# LineMixer_v1_1.net
KiCad netlist of a schematic drawn in EAGLE
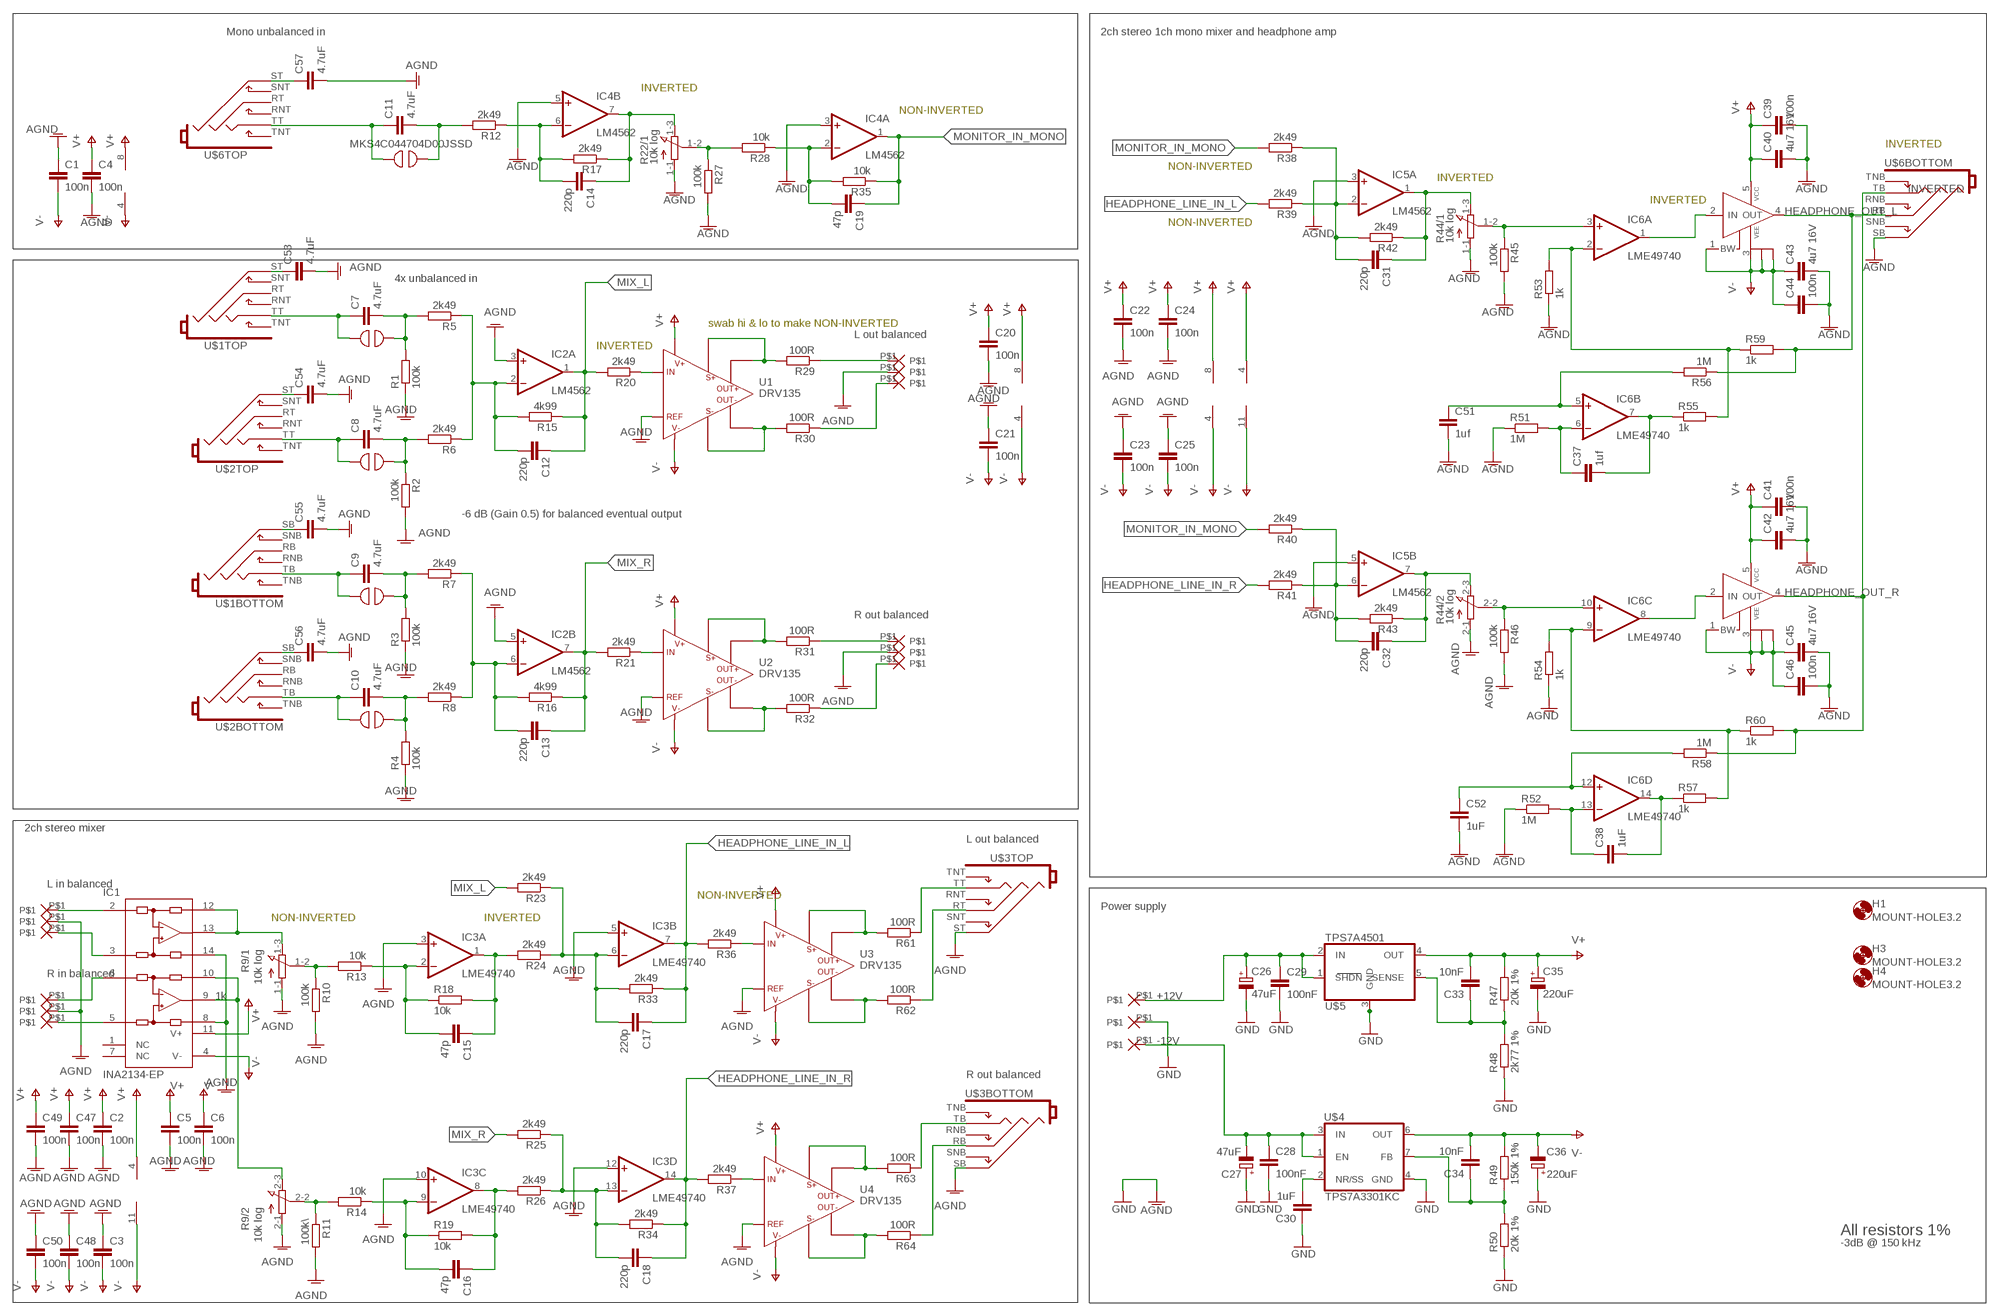
[diagram p0: schematic, sheet 1]

(export (version "E")
  (design (tool "Eeschema 10.0.6"))
  (components
    (comp (ref "C1")
      (value "100n")
      (footprint "eagle-import:C0603")
      (libsource (lib "eagle-import") (part "C-EUC0603"))
    )
    (comp (ref "C2")
      (value "100n")
      (footprint "eagle-import:C0603")
      (libsource (lib "eagle-import") (part "C-EUC0603"))
    )
    (comp (ref "C3")
      (value "100n")
      (footprint "eagle-import:C0603")
      (libsource (lib "eagle-import") (part "C-EUC0603"))
    )
    (comp (ref "C4")
      (value "100n")
      (footprint "eagle-import:C0603")
      (libsource (lib "eagle-import") (part "C-EUC0603"))
    )
    (comp (ref "C5")
      (value "100n")
      (footprint "eagle-import:C0603")
      (libsource (lib "eagle-import") (part "C-EUC0603"))
    )
    (comp (ref "C6")
      (value "100n")
      (footprint "eagle-import:C0603")
      (libsource (lib "eagle-import") (part "C-EUC0603"))
    )
    (comp (ref "C7")
      (value "4.7uF")
      (footprint "eagle-import:C15B7")
      (libsource (lib "eagle-import") (part "C15/7"))
    )
    (comp (ref "C8")
      (value "4.7uF")
      (footprint "eagle-import:C15B7")
      (libsource (lib "eagle-import") (part "C15/7"))
    )
    (comp (ref "C9")
      (value "4.7uF")
      (footprint "eagle-import:C15B7")
      (libsource (lib "eagle-import") (part "C15/7"))
    )
    (comp (ref "C10")
      (value "4.7uF")
      (footprint "eagle-import:C15B7")
      (libsource (lib "eagle-import") (part "C15/7"))
    )
    (comp (ref "C11")
      (value "4.7uF")
      (footprint "eagle-import:C15B7")
      (libsource (lib "eagle-import") (part "C15/7"))
    )
    (comp (ref "C12")
      (value "220p")
      (footprint "eagle-import:C0603K")
      (libsource (lib "eagle-import") (part "C-EUC0603K"))
    )
    (comp (ref "C13")
      (value "220p")
      (footprint "eagle-import:C0603K")
      (libsource (lib "eagle-import") (part "C-EUC0603K"))
    )
    (comp (ref "C14")
      (value "220p")
      (footprint "eagle-import:C0603K")
      (libsource (lib "eagle-import") (part "C-EUC0603K"))
    )
    (comp (ref "C15")
      (value "47p")
      (footprint "eagle-import:C0603K")
      (libsource (lib "eagle-import") (part "C-EUC0603K"))
    )
    (comp (ref "C16")
      (value "47p")
      (footprint "eagle-import:C0603K")
      (libsource (lib "eagle-import") (part "C-EUC0603K"))
    )
    (comp (ref "C17")
      (value "220p")
      (footprint "eagle-import:C0603K")
      (libsource (lib "eagle-import") (part "C-EUC0603K"))
    )
    (comp (ref "C18")
      (value "220p")
      (footprint "eagle-import:C0603K")
      (libsource (lib "eagle-import") (part "C-EUC0603K"))
    )
    (comp (ref "C19")
      (value "47p")
      (footprint "eagle-import:C0603K")
      (libsource (lib "eagle-import") (part "C-EUC0603K"))
    )
    (comp (ref "C20")
      (value "100n")
      (footprint "eagle-import:C0603")
      (libsource (lib "eagle-import") (part "C-EUC0603"))
    )
    (comp (ref "C21")
      (value "100n")
      (footprint "eagle-import:C0603")
      (libsource (lib "eagle-import") (part "C-EUC0603"))
    )
    (comp (ref "C22")
      (value "100n")
      (footprint "eagle-import:C0603")
      (libsource (lib "eagle-import") (part "C-EUC0603"))
    )
    (comp (ref "C23")
      (value "100n")
      (footprint "eagle-import:C0603")
      (libsource (lib "eagle-import") (part "C-EUC0603"))
    )
    (comp (ref "C24")
      (value "100n")
      (footprint "eagle-import:C0603")
      (libsource (lib "eagle-import") (part "C-EUC0603"))
    )
    (comp (ref "C25")
      (value "100n")
      (footprint "eagle-import:C0603")
      (libsource (lib "eagle-import") (part "C-EUC0603"))
    )
    (comp (ref "C26")
      (value "47uF")
      (footprint "eagle-import:D_7343-31R")
      (libsource (lib "eagle-import") (part "CPOL-EUD/7343-31R"))
    )
    (comp (ref "C27")
      (value "47uF")
      (footprint "eagle-import:D_7343-31R")
      (libsource (lib "eagle-import") (part "CPOL-EUD/7343-31R"))
    )
    (comp (ref "C28")
      (value "100nF")
      (footprint "eagle-import:C0603")
      (libsource (lib "eagle-import") (part "C-EUC0603"))
    )
    (comp (ref "C29")
      (value "100nF")
      (footprint "eagle-import:C0603")
      (libsource (lib "eagle-import") (part "C-EUC0603"))
    )
    (comp (ref "C30")
      (value "1uF")
      (footprint "eagle-import:C0603")
      (libsource (lib "eagle-import") (part "C-EUC0603"))
    )
    (comp (ref "C31")
      (value "220p")
      (footprint "eagle-import:C0603K")
      (libsource (lib "eagle-import") (part "C-EUC0603K"))
    )
    (comp (ref "C32")
      (value "220p")
      (footprint "eagle-import:C0603K")
      (libsource (lib "eagle-import") (part "C-EUC0603K"))
    )
    (comp (ref "C33")
      (value "10nF")
      (footprint "eagle-import:C0603")
      (libsource (lib "eagle-import") (part "C-EUC0603"))
    )
    (comp (ref "C34")
      (value "10nF")
      (footprint "eagle-import:C0603")
      (libsource (lib "eagle-import") (part "C-EUC0603"))
    )
    (comp (ref "C35")
      (value "220uF")
      (footprint "eagle-import:D_7343-31R")
      (libsource (lib "eagle-import") (part "CPOL-EUD/7343-31R"))
    )
    (comp (ref "C36")
      (value "220uF")
      (footprint "eagle-import:D_7343-31R")
      (libsource (lib "eagle-import") (part "CPOL-EUD/7343-31R"))
    )
    (comp (ref "C37")
      (value "1uf")
      (footprint "eagle-import:C0603")
      (libsource (lib "eagle-import") (part "C-EUC0603"))
    )
    (comp (ref "C38")
      (value "1uF")
      (footprint "eagle-import:C0603")
      (libsource (lib "eagle-import") (part "C-EUC0603"))
    )
    (comp (ref "C39")
      (value "100n")
      (footprint "eagle-import:C0603")
      (libsource (lib "eagle-import") (part "C-EUC0603"))
    )
    (comp (ref "C40")
      (value "4u7 16V")
      (footprint "eagle-import:C1206")
      (libsource (lib "eagle-import") (part "C-EUC1206"))
    )
    (comp (ref "C41")
      (value "100n")
      (footprint "eagle-import:C0603")
      (libsource (lib "eagle-import") (part "C-EUC0603"))
    )
    (comp (ref "C42")
      (value "4u7 16V")
      (footprint "eagle-import:C1206")
      (libsource (lib "eagle-import") (part "C-EUC1206"))
    )
    (comp (ref "C43")
      (value "4u7 16V")
      (footprint "eagle-import:C1206")
      (libsource (lib "eagle-import") (part "C-EUC1206"))
    )
    (comp (ref "C44")
      (value "100n")
      (footprint "eagle-import:C0603")
      (libsource (lib "eagle-import") (part "C-EUC0603"))
    )
    (comp (ref "C45")
      (value "4u7 16V")
      (footprint "eagle-import:C1206")
      (libsource (lib "eagle-import") (part "C-EUC1206"))
    )
    (comp (ref "C46")
      (value "100n")
      (footprint "eagle-import:C0603")
      (libsource (lib "eagle-import") (part "C-EUC0603"))
    )
    (comp (ref "C47")
      (value "100n")
      (footprint "eagle-import:C0603")
      (libsource (lib "eagle-import") (part "C-EUC0603"))
    )
    (comp (ref "C48")
      (value "100n")
      (footprint "eagle-import:C0603")
      (libsource (lib "eagle-import") (part "C-EUC0603"))
    )
    (comp (ref "C49")
      (value "100n")
      (footprint "eagle-import:C0603")
      (libsource (lib "eagle-import") (part "C-EUC0603"))
    )
    (comp (ref "C50")
      (value "100n")
      (footprint "eagle-import:C0603")
      (libsource (lib "eagle-import") (part "C-EUC0603"))
    )
    (comp (ref "C51")
      (value "1uf")
      (footprint "eagle-import:C0603")
      (libsource (lib "eagle-import") (part "C-EUC0603"))
    )
    (comp (ref "C52")
      (value "1uF")
      (footprint "eagle-import:C0603")
      (libsource (lib "eagle-import") (part "C-EUC0603"))
    )
    (comp (ref "C53")
      (value "4.7uF")
      (footprint "eagle-import:C15B7")
      (libsource (lib "eagle-import") (part "C15/7"))
    )
    (comp (ref "C54")
      (value "4.7uF")
      (footprint "eagle-import:C15B7")
      (libsource (lib "eagle-import") (part "C15/7"))
    )
    (comp (ref "C55")
      (value "4.7uF")
      (footprint "eagle-import:C15B7")
      (libsource (lib "eagle-import") (part "C15/7"))
    )
    (comp (ref "C56")
      (value "4.7uF")
      (footprint "eagle-import:C15B7")
      (libsource (lib "eagle-import") (part "C15/7"))
    )
    (comp (ref "C57")
      (value "4.7uF")
      (footprint "eagle-import:C15B7")
      (libsource (lib "eagle-import") (part "C15/7"))
    )
    (comp (ref "H1")
      (value "MOUNT-HOLE3.2")
      (footprint "eagle-import:3,2")
      (libsource (lib "eagle-import") (part "MOUNT-HOLE3.2"))
    )
    (comp (ref "H3")
      (value "MOUNT-HOLE3.2")
      (footprint "eagle-import:3,2")
      (libsource (lib "eagle-import") (part "MOUNT-HOLE3.2"))
    )
    (comp (ref "H4")
      (value "MOUNT-HOLE3.2")
      (footprint "eagle-import:3,2")
      (libsource (lib "eagle-import") (part "MOUNT-HOLE3.2"))
    )
    (comp (ref "IC1")
      (value "INA2134-EP")
      (footprint "eagle-import:SO14")
      (fields (field (name "MF") "TEXAS INSTRUMENTS") (field (name "MPN") "INA2134UA"))
      (libsource (lib "eagle-import") (part "INA2134U"))
    )
    (comp (ref "IC2")
      (value "LM4562")
      (footprint "eagle-import:SO08")
      (libsource (lib "eagle-import") (part "4558DLM"))
    )
    (comp (ref "IC3")
      (value "LME49740")
      (footprint "eagle-import:SO14")
      (libsource (lib "eagle-import") (part "TL074D"))
    )
    (comp (ref "IC4")
      (value "LM4562")
      (footprint "eagle-import:SO08")
      (libsource (lib "eagle-import") (part "4558DLM"))
    )
    (comp (ref "IC5")
      (value "LM4562")
      (footprint "eagle-import:SO08")
      (libsource (lib "eagle-import") (part "4558DLM"))
    )
    (comp (ref "IC6")
      (value "LME49740")
      (footprint "eagle-import:SO14")
      (libsource (lib "eagle-import") (part "TL074D"))
    )
    (comp (ref "IC7")
      (value "LME49600")
      (footprint "eagle-import:TS5B")
      (libsource (lib "eagle-import") (part "LME49600"))
    )
    (comp (ref "IC8")
      (value "LME49600")
      (footprint "eagle-import:TS5B")
      (libsource (lib "eagle-import") (part "LME49600"))
    )
    (comp (ref "R1")
      (value "100k")
      (footprint "eagle-import:0207_7")
      (libsource (lib "eagle-import") (part "R-EU_0207/7"))
    )
    (comp (ref "R2")
      (value "100k")
      (footprint "eagle-import:0207_7")
      (libsource (lib "eagle-import") (part "R-EU_0207/7"))
    )
    (comp (ref "R3")
      (value "100k")
      (footprint "eagle-import:0207_7")
      (libsource (lib "eagle-import") (part "R-EU_0207/7"))
    )
    (comp (ref "R4")
      (value "100k")
      (footprint "eagle-import:0207_7")
      (libsource (lib "eagle-import") (part "R-EU_0207/7"))
    )
    (comp (ref "R5")
      (value "2k49")
      (footprint "eagle-import:0207_7")
      (libsource (lib "eagle-import") (part "R-EU_0207/7"))
    )
    (comp (ref "R6")
      (value "2k49")
      (footprint "eagle-import:0207_7")
      (libsource (lib "eagle-import") (part "R-EU_0207/7"))
    )
    (comp (ref "R7")
      (value "2k49")
      (footprint "eagle-import:0207_7")
      (libsource (lib "eagle-import") (part "R-EU_0207/7"))
    )
    (comp (ref "R8")
      (value "2k49")
      (footprint "eagle-import:0207_7")
      (libsource (lib "eagle-import") (part "R-EU_0207/7"))
    )
    (comp (ref "R9")
      (value "10k log")
      (footprint "eagle-import:3RP_1610G")
      (libsource (lib "eagle-import") (part "3RP/1610G"))
    )
    (comp (ref "R10")
      (value "100k")
      (footprint "eagle-import:0207_7")
      (libsource (lib "eagle-import") (part "R-EU_0207/7"))
    )
    (comp (ref "R11")
      (value "100k\\")
      (footprint "eagle-import:0207_7")
      (libsource (lib "eagle-import") (part "R-EU_0207/7"))
    )
    (comp (ref "R12")
      (value "2k49")
      (footprint "eagle-import:0207_7")
      (libsource (lib "eagle-import") (part "R-EU_0207/7"))
    )
    (comp (ref "R13")
      (value "10k")
      (footprint "eagle-import:0207_7")
      (libsource (lib "eagle-import") (part "R-EU_0207/7"))
    )
    (comp (ref "R14")
      (value "10k")
      (footprint "eagle-import:0207_7")
      (libsource (lib "eagle-import") (part "R-EU_0207/7"))
    )
    (comp (ref "R15")
      (value "4k99")
      (footprint "eagle-import:0207_7")
      (libsource (lib "eagle-import") (part "R-EU_0207/7"))
    )
    (comp (ref "R16")
      (value "4k99")
      (footprint "eagle-import:0207_7")
      (libsource (lib "eagle-import") (part "R-EU_0207/7"))
    )
    (comp (ref "R17")
      (value "2k49")
      (footprint "eagle-import:0207_7")
      (libsource (lib "eagle-import") (part "R-EU_0207/7"))
    )
    (comp (ref "R18")
      (value "10k")
      (footprint "eagle-import:0207_7")
      (libsource (lib "eagle-import") (part "R-EU_0207/7"))
    )
    (comp (ref "R19")
      (value "10k")
      (footprint "eagle-import:0207_7")
      (libsource (lib "eagle-import") (part "R-EU_0207/7"))
    )
    (comp (ref "R20")
      (value "2k49")
      (footprint "eagle-import:0207_7")
      (libsource (lib "eagle-import") (part "R-EU_0207/7"))
    )
    (comp (ref "R21")
      (value "2k49")
      (footprint "eagle-import:0207_7")
      (libsource (lib "eagle-import") (part "R-EU_0207/7"))
    )
    (comp (ref "R22")
      (value "10k log")
      (footprint "eagle-import:3RP_1610G")
      (libsource (lib "eagle-import") (part "3RP/1610G"))
    )
    (comp (ref "R23")
      (value "2k49")
      (footprint "eagle-import:0207_7")
      (libsource (lib "eagle-import") (part "R-EU_0207/7"))
    )
    (comp (ref "R24")
      (value "2k49")
      (footprint "eagle-import:0207_7")
      (libsource (lib "eagle-import") (part "R-EU_0207/7"))
    )
    (comp (ref "R25")
      (value "2k49")
      (footprint "eagle-import:0207_7")
      (libsource (lib "eagle-import") (part "R-EU_0207/7"))
    )
    (comp (ref "R26")
      (value "2k49")
      (footprint "eagle-import:0207_7")
      (libsource (lib "eagle-import") (part "R-EU_0207/7"))
    )
    (comp (ref "R27")
      (value "100k")
      (footprint "eagle-import:0207_7")
      (libsource (lib "eagle-import") (part "R-EU_0207/7"))
    )
    (comp (ref "R28")
      (value "10k")
      (footprint "eagle-import:0207_7")
      (libsource (lib "eagle-import") (part "R-EU_0207/7"))
    )
    (comp (ref "R29")
      (value "100R")
      (footprint "eagle-import:0207_7")
      (libsource (lib "eagle-import") (part "R-EU_0207/7"))
    )
    (comp (ref "R30")
      (value "100R")
      (footprint "eagle-import:0207_7")
      (libsource (lib "eagle-import") (part "R-EU_0207/7"))
    )
    (comp (ref "R31")
      (value "100R")
      (footprint "eagle-import:0207_7")
      (libsource (lib "eagle-import") (part "R-EU_0207/7"))
    )
    (comp (ref "R32")
      (value "100R")
      (footprint "eagle-import:0207_7")
      (libsource (lib "eagle-import") (part "R-EU_0207/7"))
    )
    (comp (ref "R33")
      (value "2k49")
      (footprint "eagle-import:0207_7")
      (libsource (lib "eagle-import") (part "R-EU_0207/7"))
    )
    (comp (ref "R34")
      (value "2k49")
      (footprint "eagle-import:0207_7")
      (libsource (lib "eagle-import") (part "R-EU_0207/7"))
    )
    (comp (ref "R35")
      (value "10k")
      (footprint "eagle-import:0207_7")
      (libsource (lib "eagle-import") (part "R-EU_0207/7"))
    )
    (comp (ref "R36")
      (value "2k49")
      (footprint "eagle-import:0207_7")
      (libsource (lib "eagle-import") (part "R-EU_0207/7"))
    )
    (comp (ref "R37")
      (value "2k49")
      (footprint "eagle-import:0207_7")
      (libsource (lib "eagle-import") (part "R-EU_0207/7"))
    )
    (comp (ref "R38")
      (value "2k49")
      (footprint "eagle-import:0207_7")
      (libsource (lib "eagle-import") (part "R-EU_0207/7"))
    )
    (comp (ref "R39")
      (value "2k49")
      (footprint "eagle-import:0207_7")
      (libsource (lib "eagle-import") (part "R-EU_0207/7"))
    )
    (comp (ref "R40")
      (value "2k49")
      (footprint "eagle-import:0207_7")
      (libsource (lib "eagle-import") (part "R-EU_0207/7"))
    )
    (comp (ref "R41")
      (value "2k49")
      (footprint "eagle-import:0207_7")
      (libsource (lib "eagle-import") (part "R-EU_0207/7"))
    )
    (comp (ref "R42")
      (value "2k49")
      (footprint "eagle-import:0207_7")
      (libsource (lib "eagle-import") (part "R-EU_0207/7"))
    )
    (comp (ref "R43")
      (value "2k49")
      (footprint "eagle-import:0207_7")
      (libsource (lib "eagle-import") (part "R-EU_0207/7"))
    )
    (comp (ref "R44")
      (value "10k log")
      (footprint "eagle-import:3RP_1610G")
      (libsource (lib "eagle-import") (part "3RP/1610G"))
    )
    (comp (ref "R45")
      (value "100k")
      (footprint "eagle-import:0207_7")
      (libsource (lib "eagle-import") (part "R-EU_0207/7"))
    )
    (comp (ref "R46")
      (value "100k")
      (footprint "eagle-import:0207_7")
      (libsource (lib "eagle-import") (part "R-EU_0207/7"))
    )
    (comp (ref "R47")
      (value "20k 1%")
      (footprint "eagle-import:R0603")
      (libsource (lib "eagle-import") (part "R-EU_R0603"))
    )
    (comp (ref "R48")
      (value "2k77 1%")
      (footprint "eagle-import:R0603")
      (libsource (lib "eagle-import") (part "R-EU_R0603"))
    )
    (comp (ref "R49")
      (value "150k 1%")
      (footprint "eagle-import:R0603")
      (libsource (lib "eagle-import") (part "R-EU_R0603"))
    )
    (comp (ref "R50")
      (value "20k 1%")
      (footprint "eagle-import:R0603")
      (libsource (lib "eagle-import") (part "R-EU_R0603"))
    )
    (comp (ref "R51")
      (value "1M")
      (footprint "eagle-import:0207_7")
      (libsource (lib "eagle-import") (part "R-EU_0207/7"))
    )
    (comp (ref "R52")
      (value "1M")
      (footprint "eagle-import:0207_7")
      (libsource (lib "eagle-import") (part "R-EU_0207/7"))
    )
    (comp (ref "R53")
      (value "1k")
      (footprint "eagle-import:0207_7")
      (libsource (lib "eagle-import") (part "R-EU_0207/7"))
    )
    (comp (ref "R54")
      (value "1k")
      (footprint "eagle-import:0207_7")
      (libsource (lib "eagle-import") (part "R-EU_0207/7"))
    )
    (comp (ref "R55")
      (value "1k")
      (footprint "eagle-import:0207_7")
      (libsource (lib "eagle-import") (part "R-EU_0207/7"))
    )
    (comp (ref "R56")
      (value "1M")
      (footprint "eagle-import:0207_7")
      (libsource (lib "eagle-import") (part "R-EU_0207/7"))
    )
    (comp (ref "R57")
      (value "1k")
      (footprint "eagle-import:0207_7")
      (libsource (lib "eagle-import") (part "R-EU_0207/7"))
    )
    (comp (ref "R58")
      (value "1M")
      (footprint "eagle-import:0207_7")
      (libsource (lib "eagle-import") (part "R-EU_0207/7"))
    )
    (comp (ref "R59")
      (value "1k")
      (footprint "eagle-import:0207_7")
      (libsource (lib "eagle-import") (part "R-EU_0207/7"))
    )
    (comp (ref "R60")
      (value "1k")
      (footprint "eagle-import:0207_7")
      (libsource (lib "eagle-import") (part "R-EU_0207/7"))
    )
    (comp (ref "R61")
      (value "100R")
      (footprint "eagle-import:0207_7")
      (libsource (lib "eagle-import") (part "R-EU_0207/7"))
    )
    (comp (ref "R62")
      (value "100R")
      (footprint "eagle-import:0207_7")
      (libsource (lib "eagle-import") (part "R-EU_0207/7"))
    )
    (comp (ref "R63")
      (value "100R")
      (footprint "eagle-import:0207_7")
      (libsource (lib "eagle-import") (part "R-EU_0207/7"))
    )
    (comp (ref "R64")
      (value "100R")
      (footprint "eagle-import:0207_7")
      (libsource (lib "eagle-import") (part "R-EU_0207/7"))
    )
    (comp (ref "S1")
      (value "SOLDERLINK")
      (footprint "eagle-import:SOLDERLINK")
      (libsource (lib "eagle-import") (part "SOLDERLINK"))
    )
    (comp (ref "S2")
      (value "SOLDERLINK")
      (footprint "eagle-import:SOLDERLINK")
      (libsource (lib "eagle-import") (part "SOLDERLINK"))
    )
    (comp (ref "S3")
      (value "SOLDERLINK")
      (footprint "eagle-import:SOLDERLINK")
      (libsource (lib "eagle-import") (part "SOLDERLINK"))
    )
    (comp (ref "S4")
      (value "SOLDERLINK")
      (footprint "eagle-import:SOLDERLINK")
      (libsource (lib "eagle-import") (part "SOLDERLINK"))
    )
    (comp (ref "S5")
      (value "SOLDERLINK")
      (footprint "eagle-import:SOLDERLINK")
      (libsource (lib "eagle-import") (part "SOLDERLINK"))
    )
    (comp (ref "U$1")
      (value "NSJ12HF-1")
      (footprint "eagle-import:NSJ12HF-1")
      (libsource (lib "eagle-import") (part "NSJ12HF-1"))
    )
    (comp (ref "U$2")
      (value "NSJ12HF-1")
      (footprint "eagle-import:NSJ12HF-1")
      (libsource (lib "eagle-import") (part "NSJ12HF-1"))
    )
    (comp (ref "U$3")
      (value "NSJ12HF-1")
      (footprint "eagle-import:NSJ12HF-1")
      (libsource (lib "eagle-import") (part "NSJ12HF-1"))
    )
    (comp (ref "U$4")
      (value "TPS7A3301KC")
      (footprint "eagle-import:TO220-7")
      (libsource (lib "eagle-import") (part "TPS7A3301KC"))
    )
    (comp (ref "U$5")
      (value "TPS7A4501")
      (footprint "eagle-import:SOT223-5")
      (libsource (lib "eagle-import") (part "TPS7A4501"))
    )
    (comp (ref "U$6")
      (value "NSJ12HF-1")
      (footprint "eagle-import:NSJ12HF-1")
      (libsource (lib "eagle-import") (part "NSJ12HF-1"))
    )
    (comp (ref "U$7")
      (value "PAD1.5MM")
      (footprint "eagle-import:PAD_1.5MM")
      (libsource (lib "eagle-import") (part "PAD1.5MM"))
    )
    (comp (ref "U$8")
      (value "PAD1.5MM")
      (footprint "eagle-import:PAD_1.5MM")
      (libsource (lib "eagle-import") (part "PAD1.5MM"))
    )
    (comp (ref "U$10")
      (value "PAD1.5MM")
      (footprint "eagle-import:PAD_1.5MM")
      (libsource (lib "eagle-import") (part "PAD1.5MM"))
    )
    (comp (ref "U$11")
      (value "PAD1.5MM")
      (footprint "eagle-import:PAD_1.5MM")
      (libsource (lib "eagle-import") (part "PAD1.5MM"))
    )
    (comp (ref "U$12")
      (value "PAD1.5MM")
      (footprint "eagle-import:PAD_1.5MM")
      (libsource (lib "eagle-import") (part "PAD1.5MM"))
    )
    (comp (ref "U$13")
      (value "PAD1.5MM")
      (footprint "eagle-import:PAD_1.5MM")
      (libsource (lib "eagle-import") (part "PAD1.5MM"))
    )
    (comp (ref "U$14")
      (value "PAD1.5MM")
      (footprint "eagle-import:PAD_1.5MM")
      (libsource (lib "eagle-import") (part "PAD1.5MM"))
    )
    (comp (ref "U$15")
      (value "PAD1.5MM")
      (footprint "eagle-import:PAD_1.5MM")
      (libsource (lib "eagle-import") (part "PAD1.5MM"))
    )
    (comp (ref "U$16")
      (value "PAD1.5MM")
      (footprint "eagle-import:PAD_1.5MM")
      (libsource (lib "eagle-import") (part "PAD1.5MM"))
    )
    (comp (ref "U$17")
      (value "PAD1.5MM")
      (footprint "eagle-import:PAD_1.5MM")
      (libsource (lib "eagle-import") (part "PAD1.5MM"))
    )
    (comp (ref "U$18")
      (value "PAD1.5MM")
      (footprint "eagle-import:PAD_1.5MM")
      (libsource (lib "eagle-import") (part "PAD1.5MM"))
    )
    (comp (ref "U$19")
      (value "PAD1.5MM")
      (footprint "eagle-import:PAD_1.5MM")
      (libsource (lib "eagle-import") (part "PAD1.5MM"))
    )
    (comp (ref "U$20")
      (value "PAD1.5MM")
      (footprint "eagle-import:PAD_1.5MM")
      (libsource (lib "eagle-import") (part "PAD1.5MM"))
    )
    (comp (ref "U$21")
      (value "PAD1.5MM")
      (footprint "eagle-import:PAD_1.5MM")
      (libsource (lib "eagle-import") (part "PAD1.5MM"))
    )
    (comp (ref "U$22")
      (value "PAD1.5MM")
      (footprint "eagle-import:PAD_1.5MM")
      (libsource (lib "eagle-import") (part "PAD1.5MM"))
    )
    (comp (ref "U1")
      (value "DRV135")
      (footprint "eagle-import:SO-8")
      (libsource (lib "eagle-import") (part "DRV134SO-8"))
    )
    (comp (ref "U2")
      (value "DRV135")
      (footprint "eagle-import:SO-8")
      (libsource (lib "eagle-import") (part "DRV134SO-8"))
    )
    (comp (ref "U3")
      (value "DRV135")
      (footprint "eagle-import:SO-8")
      (libsource (lib "eagle-import") (part "DRV134SO-8"))
    )
    (comp (ref "U4")
      (value "DRV135")
      (footprint "eagle-import:SO-8")
      (libsource (lib "eagle-import") (part "DRV134SO-8"))
    )
  )
  (nets
    (net (code "1") (name "/+12V") (class "Default")
      (node (ref "C26") (pin "+") (pinfunction "+_+") (pintype "passive"))
      (node (ref "C29") (pin "1") (pinfunction "1_1") (pintype "passive"))
      (node (ref "U$20") (pin "P$1") (pinfunction "P$1_P$1") (pintype "bidirectional"))
      (node (ref "U$5") (pin "1") (pinfunction "SHDN_1") (pintype "input"))
      (node (ref "U$5") (pin "2") (pinfunction "IN_2") (pintype "power_in"))
    )
    (net (code "2") (name "/-12V") (class "Default")
      (node (ref "C27") (pin "-") (pinfunction "-_-") (pintype "passive"))
      (node (ref "C28") (pin "1") (pinfunction "1_1") (pintype "passive"))
      (node (ref "U$22") (pin "P$1") (pinfunction "P$1_P$1") (pintype "bidirectional"))
      (node (ref "U$4") (pin "1") (pinfunction "EN_1") (pintype "bidirectional"))
      (node (ref "U$4") (pin "3") (pinfunction "IN_3") (pintype "bidirectional"))
    )
    (net (code "3") (name "/HEADPHONE_OUT_L") (class "Default")
      (node (ref "IC7") (pin "4") (pinfunction "OUT_4") (pintype "output"))
      (node (ref "R56") (pin "1") (pinfunction "1_1") (pintype "passive"))
      (node (ref "R59") (pin "2") (pinfunction "2_2") (pintype "passive"))
      (node (ref "U$6") (pin "RB") (pinfunction "R_RB") (pintype "bidirectional"))
    )
    (net (code "4") (name "/HEADPHONE_OUT_R") (class "Default")
      (node (ref "IC8") (pin "4") (pinfunction "OUT_4") (pintype "output"))
      (node (ref "R58") (pin "1") (pinfunction "1_1") (pintype "passive"))
      (node (ref "R60") (pin "2") (pinfunction "2_2") (pintype "passive"))
      (node (ref "U$6") (pin "TB") (pinfunction "T_TB") (pintype "bidirectional"))
    )
    (net (code "5") (name "AGND") (class "Default")
      (node (ref "C1") (pin "1") (pinfunction "1_1") (pintype "passive"))
      (node (ref "C2") (pin "2") (pinfunction "2_2") (pintype "passive"))
      (node (ref "C20") (pin "2") (pinfunction "2_2") (pintype "passive"))
      (node (ref "C21") (pin "1") (pinfunction "1_1") (pintype "passive"))
      (node (ref "C22") (pin "2") (pinfunction "2_2") (pintype "passive"))
      (node (ref "C23") (pin "1") (pinfunction "1_1") (pintype "passive"))
      (node (ref "C24") (pin "2") (pinfunction "2_2") (pintype "passive"))
      (node (ref "C25") (pin "1") (pinfunction "1_1") (pintype "passive"))
      (node (ref "C26") (pin "-") (pinfunction "-_-") (pintype "passive"))
      (node (ref "C27") (pin "+") (pinfunction "+_+") (pintype "passive"))
      (node (ref "C28") (pin "2") (pinfunction "2_2") (pintype "passive"))
      (node (ref "C29") (pin "2") (pinfunction "2_2") (pintype "passive"))
      (node (ref "C3") (pin "1") (pinfunction "1_1") (pintype "passive"))
      (node (ref "C30") (pin "1") (pinfunction "1_1") (pintype "passive"))
      (node (ref "C35") (pin "-") (pinfunction "-_-") (pintype "passive"))
      (node (ref "C36") (pin "+") (pinfunction "+_+") (pintype "passive"))
      (node (ref "C39") (pin "2") (pinfunction "2_2") (pintype "passive"))
      (node (ref "C4") (pin "2") (pinfunction "2_2") (pintype "passive"))
      (node (ref "C40") (pin "2") (pinfunction "2_2") (pintype "passive"))
      (node (ref "C41") (pin "2") (pinfunction "2_2") (pintype "passive"))
      (node (ref "C42") (pin "2") (pinfunction "2_2") (pintype "passive"))
      (node (ref "C43") (pin "2") (pinfunction "2_2") (pintype "passive"))
      (node (ref "C44") (pin "2") (pinfunction "2_2") (pintype "passive"))
      (node (ref "C45") (pin "2") (pinfunction "2_2") (pintype "passive"))
      (node (ref "C46") (pin "2") (pinfunction "2_2") (pintype "passive"))
      (node (ref "C47") (pin "2") (pinfunction "2_2") (pintype "passive"))
      (node (ref "C48") (pin "1") (pinfunction "1_1") (pintype "passive"))
      (node (ref "C49") (pin "2") (pinfunction "2_2") (pintype "passive"))
      (node (ref "C5") (pin "2") (pinfunction "2_2") (pintype "passive"))
      (node (ref "C50") (pin "1") (pinfunction "1_1") (pintype "passive"))
      (node (ref "C51") (pin "2") (pinfunction "2_2") (pintype "passive"))
      (node (ref "C52") (pin "2") (pinfunction "2_2") (pintype "passive"))
      (node (ref "C53") (pin "2") (pinfunction "2_2") (pintype "passive"))
      (node (ref "C54") (pin "2") (pinfunction "2_2") (pintype "passive"))
      (node (ref "C55") (pin "2") (pinfunction "2_2") (pintype "passive"))
      (node (ref "C56") (pin "2") (pinfunction "2_2") (pintype "passive"))
      (node (ref "C57") (pin "2") (pinfunction "2_2") (pintype "passive"))
      (node (ref "C6") (pin "2") (pinfunction "2_2") (pintype "passive"))
      (node (ref "IC1") (pin "14") (pinfunction "REFA_14") (pintype "passive"))
      (node (ref "IC1") (pin "8") (pinfunction "REFB_8") (pintype "passive"))
      (node (ref "IC2") (pin "3") (pinfunction "+IN_3") (pintype "input"))
      (node (ref "IC2") (pin "5") (pinfunction "+IN_5") (pintype "input"))
      (node (ref "IC3") (pin "10") (pinfunction "+IN_10") (pintype "input"))
      (node (ref "IC3") (pin "12") (pinfunction "+IN_12") (pintype "input"))
      (node (ref "IC3") (pin "3") (pinfunction "+IN_3") (pintype "input"))
      (node (ref "IC3") (pin "5") (pinfunction "+IN_5") (pintype "input"))
      (node (ref "IC4") (pin "3") (pinfunction "+IN_3") (pintype "input"))
      (node (ref "IC4") (pin "5") (pinfunction "+IN_5") (pintype "input"))
      (node (ref "IC5") (pin "3") (pinfunction "+IN_3") (pintype "input"))
      (node (ref "IC5") (pin "5") (pinfunction "+IN_5") (pintype "input"))
      (node (ref "R1") (pin "1") (pinfunction "1_1") (pintype "passive"))
      (node (ref "R10") (pin "2") (pinfunction "2_2") (pintype "passive"))
      (node (ref "R11") (pin "2") (pinfunction "2_2") (pintype "passive"))
      (node (ref "R2") (pin "2") (pinfunction "2_2") (pintype "passive"))
      (node (ref "R22") (pin "1-1") (pinfunction "A_1-1") (pintype "passive"))
      (node (ref "R27") (pin "2") (pinfunction "2_2") (pintype "passive"))
      (node (ref "R3") (pin "1") (pinfunction "1_1") (pintype "passive"))
      (node (ref "R4") (pin "1") (pinfunction "1_1") (pintype "passive"))
      (node (ref "R44") (pin "1-1") (pinfunction "A_1-1") (pintype "passive"))
      (node (ref "R44") (pin "2-1") (pinfunction "A_2-1") (pintype "passive"))
      (node (ref "R45") (pin "2") (pinfunction "2_2") (pintype "passive"))
      (node (ref "R46") (pin "2") (pinfunction "2_2") (pintype "passive"))
      (node (ref "R48") (pin "1") (pinfunction "1_1") (pintype "passive"))
      (node (ref "R50") (pin "1") (pinfunction "1_1") (pintype "passive"))
      (node (ref "R51") (pin "1") (pinfunction "1_1") (pintype "passive"))
      (node (ref "R52") (pin "1") (pinfunction "1_1") (pintype "passive"))
      (node (ref "R53") (pin "1") (pinfunction "1_1") (pintype "passive"))
      (node (ref "R54") (pin "1") (pinfunction "1_1") (pintype "passive"))
      (node (ref "R9") (pin "1-1") (pinfunction "A_1-1") (pintype "passive"))
      (node (ref "R9") (pin "2-1") (pinfunction "A_2-1") (pintype "passive"))
      (node (ref "U$12") (pin "P$1") (pinfunction "P$1_P$1") (pintype "bidirectional"))
      (node (ref "U$15") (pin "P$1") (pinfunction "P$1_P$1") (pintype "bidirectional"))
      (node (ref "U$18") (pin "P$1") (pinfunction "P$1_P$1") (pintype "bidirectional"))
      (node (ref "U$21") (pin "P$1") (pinfunction "P$1_P$1") (pintype "bidirectional"))
      (node (ref "U$3") (pin "SB") (pinfunction "S_SB") (pintype "bidirectional"))
      (node (ref "U$3") (pin "ST") (pinfunction "S_ST") (pintype "bidirectional"))
      (node (ref "U$4") (pin "4") (pinfunction "GND_4") (pintype "bidirectional"))
      (node (ref "U$5") (pin "3") (pinfunction "GND_3") (pintype "power_in"))
      (node (ref "U$5") (pin "TAB") (pinfunction "GND_TAB") (pintype "power_in"))
      (node (ref "U$6") (pin "SB") (pinfunction "S_SB") (pintype "bidirectional"))
      (node (ref "U$8") (pin "P$1") (pinfunction "P$1_P$1") (pintype "bidirectional"))
      (node (ref "U1") (pin "P3") (pinfunction "REF_P3") (pintype "input"))
      (node (ref "U2") (pin "P3") (pinfunction "REF_P3") (pintype "input"))
      (node (ref "U3") (pin "P3") (pinfunction "REF_P3") (pintype "input"))
      (node (ref "U4") (pin "P3") (pinfunction "REF_P3") (pintype "input"))
    )
    (net (code "6") (name "HEADPHONE_LINE_IN_L") (class "Default")
      (node (ref "C17") (pin "1") (pinfunction "1_1") (pintype "passive"))
      (node (ref "IC3") (pin "7") (pinfunction "OUT_7") (pintype "output"))
      (node (ref "R33") (pin "1") (pinfunction "1_1") (pintype "passive"))
      (node (ref "R36") (pin "2") (pinfunction "2_2") (pintype "passive"))
      (node (ref "R39") (pin "2") (pinfunction "2_2") (pintype "passive"))
    )
    (net (code "7") (name "HEADPHONE_LINE_IN_R") (class "Default")
      (node (ref "C18") (pin "1") (pinfunction "1_1") (pintype "passive"))
      (node (ref "IC3") (pin "14") (pinfunction "OUT_14") (pintype "output"))
      (node (ref "R34") (pin "1") (pinfunction "1_1") (pintype "passive"))
      (node (ref "R37") (pin "2") (pinfunction "2_2") (pintype "passive"))
      (node (ref "R41") (pin "2") (pinfunction "2_2") (pintype "passive"))
    )
    (net (code "8") (name "MIX_L") (class "Default")
      (node (ref "C12") (pin "1") (pinfunction "1_1") (pintype "passive"))
      (node (ref "IC2") (pin "1") (pinfunction "OUT_1") (pintype "output"))
      (node (ref "R15") (pin "1") (pinfunction "1_1") (pintype "passive"))
      (node (ref "R20") (pin "2") (pinfunction "2_2") (pintype "passive"))
      (node (ref "R23") (pin "2") (pinfunction "2_2") (pintype "passive"))
    )
    (net (code "9") (name "MIX_R") (class "Default")
      (node (ref "C13") (pin "1") (pinfunction "1_1") (pintype "passive"))
      (node (ref "IC2") (pin "7") (pinfunction "OUT_7") (pintype "output"))
      (node (ref "R16") (pin "1") (pinfunction "1_1") (pintype "passive"))
      (node (ref "R21") (pin "2") (pinfunction "2_2") (pintype "passive"))
      (node (ref "R25") (pin "2") (pinfunction "2_2") (pintype "passive"))
    )
    (net (code "10") (name "MONITOR_IN_MONO") (class "Default")
      (node (ref "C19") (pin "1") (pinfunction "1_1") (pintype "passive"))
      (node (ref "IC4") (pin "1") (pinfunction "OUT_1") (pintype "output"))
      (node (ref "R35") (pin "1") (pinfunction "1_1") (pintype "passive"))
      (node (ref "R38") (pin "2") (pinfunction "2_2") (pintype "passive"))
      (node (ref "R40") (pin "2") (pinfunction "2_2") (pintype "passive"))
    )
    (net (code "11") (name "Net-(C7-Pad2)") (class "Default")
      (node (ref "C7") (pin "2") (pinfunction "2_2") (pintype "passive"))
      (node (ref "R1") (pin "2") (pinfunction "2_2") (pintype "passive"))
      (node (ref "R5") (pin "2") (pinfunction "2_2") (pintype "passive"))
      (node (ref "S1") (pin "P$1") (pinfunction "P$1_P$1") (pintype "passive"))
    )
    (net (code "12") (name "Net-(C8-Pad2)") (class "Default")
      (node (ref "C8") (pin "2") (pinfunction "2_2") (pintype "passive"))
      (node (ref "R2") (pin "1") (pinfunction "1_1") (pintype "passive"))
      (node (ref "R6") (pin "2") (pinfunction "2_2") (pintype "passive"))
      (node (ref "S2") (pin "P$1") (pinfunction "P$1_P$1") (pintype "passive"))
    )
    (net (code "13") (name "Net-(C9-Pad2)") (class "Default")
      (node (ref "C9") (pin "2") (pinfunction "2_2") (pintype "passive"))
      (node (ref "R3") (pin "2") (pinfunction "2_2") (pintype "passive"))
      (node (ref "R7") (pin "2") (pinfunction "2_2") (pintype "passive"))
      (node (ref "S3") (pin "P$1") (pinfunction "P$1_P$1") (pintype "passive"))
    )
    (net (code "14") (name "Net-(C10-Pad2)") (class "Default")
      (node (ref "C10") (pin "2") (pinfunction "2_2") (pintype "passive"))
      (node (ref "R4") (pin "2") (pinfunction "2_2") (pintype "passive"))
      (node (ref "R8") (pin "2") (pinfunction "2_2") (pintype "passive"))
      (node (ref "S4") (pin "P$1") (pinfunction "P$1_P$1") (pintype "passive"))
    )
    (net (code "15") (name "Net-(C11-Pad2)") (class "Default")
      (node (ref "C11") (pin "2") (pinfunction "2_2") (pintype "passive"))
      (node (ref "R12") (pin "2") (pinfunction "2_2") (pintype "passive"))
      (node (ref "S5") (pin "P$1") (pinfunction "P$1_P$1") (pintype "passive"))
    )
    (net (code "16") (name "Net-(IC1-+INA)") (class "Default")
      (node (ref "IC1") (pin "3") (pinfunction "+INA_3") (pintype "input"))
      (node (ref "U$10") (pin "P$1") (pinfunction "P$1_P$1") (pintype "bidirectional"))
    )
    (net (code "17") (name "Net-(IC1-+INB)") (class "Default")
      (node (ref "IC1") (pin "5") (pinfunction "+INB_5") (pintype "input"))
      (node (ref "U$13") (pin "P$1") (pinfunction "P$1_P$1") (pintype "bidirectional"))
    )
    (net (code "18") (name "Net-(IC1--INA)") (class "Default")
      (node (ref "IC1") (pin "2") (pinfunction "-INA_2") (pintype "input"))
      (node (ref "U$7") (pin "P$1") (pinfunction "P$1_P$1") (pintype "bidirectional"))
    )
    (net (code "19") (name "Net-(IC1--INB)") (class "Default")
      (node (ref "IC1") (pin "6") (pinfunction "-INB_6") (pintype "input"))
      (node (ref "U$11") (pin "P$1") (pinfunction "P$1_P$1") (pintype "bidirectional"))
    )
    (net (code "20") (name "Net-(IC1-OUTA)") (class "Default")
      (node (ref "IC1") (pin "12") (pinfunction "SENSEA_12") (pintype "passive"))
      (node (ref "IC1") (pin "13") (pinfunction "OUTA_13") (pintype "output"))
      (node (ref "R9") (pin "1-3") (pinfunction "E_1-3") (pintype "passive"))
    )
    (net (code "21") (name "Net-(IC1-OUTB)") (class "Default")
      (node (ref "IC1") (pin "10") (pinfunction "SENSEB_10") (pintype "passive"))
      (node (ref "IC1") (pin "9") (pinfunction "OUTB_9") (pintype "output"))
      (node (ref "R9") (pin "2-3") (pinfunction "E_2-3") (pintype "passive"))
    )
    (net (code "22") (name "Net-(IC2A--IN)") (class "Default")
      (node (ref "C12") (pin "2") (pinfunction "2_2") (pintype "passive"))
      (node (ref "IC2") (pin "2") (pinfunction "-IN_2") (pintype "input"))
      (node (ref "R15") (pin "2") (pinfunction "2_2") (pintype "passive"))
      (node (ref "R5") (pin "1") (pinfunction "1_1") (pintype "passive"))
      (node (ref "R6") (pin "1") (pinfunction "1_1") (pintype "passive"))
    )
    (net (code "23") (name "Net-(IC2B--IN)") (class "Default")
      (node (ref "C13") (pin "2") (pinfunction "2_2") (pintype "passive"))
      (node (ref "IC2") (pin "6") (pinfunction "-IN_6") (pintype "input"))
      (node (ref "R16") (pin "2") (pinfunction "2_2") (pintype "passive"))
      (node (ref "R7") (pin "1") (pinfunction "1_1") (pintype "passive"))
      (node (ref "R8") (pin "1") (pinfunction "1_1") (pintype "passive"))
    )
    (net (code "24") (name "Net-(IC3A--IN)") (class "Default")
      (node (ref "C15") (pin "2") (pinfunction "2_2") (pintype "passive"))
      (node (ref "IC3") (pin "2") (pinfunction "-IN_2") (pintype "input"))
      (node (ref "R13") (pin "1") (pinfunction "1_1") (pintype "passive"))
      (node (ref "R18") (pin "1") (pinfunction "1_1") (pintype "passive"))
    )
    (net (code "25") (name "Net-(IC3A-OUT)") (class "Default")
      (node (ref "C15") (pin "1") (pinfunction "1_1") (pintype "passive"))
      (node (ref "IC3") (pin "1") (pinfunction "OUT_1") (pintype "output"))
      (node (ref "R18") (pin "2") (pinfunction "2_2") (pintype "passive"))
      (node (ref "R24") (pin "2") (pinfunction "2_2") (pintype "passive"))
    )
    (net (code "26") (name "Net-(IC3B--IN)") (class "Default")
      (node (ref "C17") (pin "2") (pinfunction "2_2") (pintype "passive"))
      (node (ref "IC3") (pin "6") (pinfunction "-IN_6") (pintype "input"))
      (node (ref "R23") (pin "1") (pinfunction "1_1") (pintype "passive"))
      (node (ref "R24") (pin "1") (pinfunction "1_1") (pintype "passive"))
      (node (ref "R33") (pin "2") (pinfunction "2_2") (pintype "passive"))
    )
    (net (code "27") (name "Net-(IC3C--IN)") (class "Default")
      (node (ref "C16") (pin "2") (pinfunction "2_2") (pintype "passive"))
      (node (ref "IC3") (pin "9") (pinfunction "-IN_9") (pintype "input"))
      (node (ref "R14") (pin "1") (pinfunction "1_1") (pintype "passive"))
      (node (ref "R19") (pin "1") (pinfunction "1_1") (pintype "passive"))
    )
    (net (code "28") (name "Net-(IC3C-OUT)") (class "Default")
      (node (ref "C16") (pin "1") (pinfunction "1_1") (pintype "passive"))
      (node (ref "IC3") (pin "8") (pinfunction "OUT_8") (pintype "output"))
      (node (ref "R19") (pin "2") (pinfunction "2_2") (pintype "passive"))
      (node (ref "R26") (pin "2") (pinfunction "2_2") (pintype "passive"))
    )
    (net (code "29") (name "Net-(IC3D--IN)") (class "Default")
      (node (ref "C18") (pin "2") (pinfunction "2_2") (pintype "passive"))
      (node (ref "IC3") (pin "13") (pinfunction "-IN_13") (pintype "input"))
      (node (ref "R25") (pin "1") (pinfunction "1_1") (pintype "passive"))
      (node (ref "R26") (pin "1") (pinfunction "1_1") (pintype "passive"))
      (node (ref "R34") (pin "2") (pinfunction "2_2") (pintype "passive"))
    )
    (net (code "30") (name "Net-(IC4A--IN)") (class "Default")
      (node (ref "C19") (pin "2") (pinfunction "2_2") (pintype "passive"))
      (node (ref "IC4") (pin "2") (pinfunction "-IN_2") (pintype "input"))
      (node (ref "R28") (pin "1") (pinfunction "1_1") (pintype "passive"))
      (node (ref "R35") (pin "2") (pinfunction "2_2") (pintype "passive"))
    )
    (net (code "31") (name "Net-(IC4B--IN)") (class "Default")
      (node (ref "C14") (pin "2") (pinfunction "2_2") (pintype "passive"))
      (node (ref "IC4") (pin "6") (pinfunction "-IN_6") (pintype "input"))
      (node (ref "R12") (pin "1") (pinfunction "1_1") (pintype "passive"))
      (node (ref "R17") (pin "2") (pinfunction "2_2") (pintype "passive"))
    )
    (net (code "32") (name "Net-(IC4B-OUT)") (class "Default")
      (node (ref "C14") (pin "1") (pinfunction "1_1") (pintype "passive"))
      (node (ref "IC4") (pin "7") (pinfunction "OUT_7") (pintype "output"))
      (node (ref "R17") (pin "1") (pinfunction "1_1") (pintype "passive"))
      (node (ref "R22") (pin "1-3") (pinfunction "E_1-3") (pintype "passive"))
    )
    (net (code "33") (name "Net-(IC5A--IN)") (class "Default")
      (node (ref "C31") (pin "2") (pinfunction "2_2") (pintype "passive"))
      (node (ref "IC5") (pin "2") (pinfunction "-IN_2") (pintype "input"))
      (node (ref "R38") (pin "1") (pinfunction "1_1") (pintype "passive"))
      (node (ref "R39") (pin "1") (pinfunction "1_1") (pintype "passive"))
      (node (ref "R42") (pin "2") (pinfunction "2_2") (pintype "passive"))
    )
    (net (code "34") (name "Net-(IC5A-OUT)") (class "Default")
      (node (ref "C31") (pin "1") (pinfunction "1_1") (pintype "passive"))
      (node (ref "IC5") (pin "1") (pinfunction "OUT_1") (pintype "output"))
      (node (ref "R42") (pin "1") (pinfunction "1_1") (pintype "passive"))
      (node (ref "R44") (pin "1-3") (pinfunction "E_1-3") (pintype "passive"))
    )
    (net (code "35") (name "Net-(IC5B--IN)") (class "Default")
      (node (ref "C32") (pin "2") (pinfunction "2_2") (pintype "passive"))
      (node (ref "IC5") (pin "6") (pinfunction "-IN_6") (pintype "input"))
      (node (ref "R40") (pin "1") (pinfunction "1_1") (pintype "passive"))
      (node (ref "R41") (pin "1") (pinfunction "1_1") (pintype "passive"))
      (node (ref "R43") (pin "2") (pinfunction "2_2") (pintype "passive"))
    )
    (net (code "36") (name "Net-(IC5B-OUT)") (class "Default")
      (node (ref "C32") (pin "1") (pinfunction "1_1") (pintype "passive"))
      (node (ref "IC5") (pin "7") (pinfunction "OUT_7") (pintype "output"))
      (node (ref "R43") (pin "1") (pinfunction "1_1") (pintype "passive"))
      (node (ref "R44") (pin "2-3") (pinfunction "E_2-3") (pintype "passive"))
    )
    (net (code "37") (name "Net-(IC6A-+IN)") (class "Default")
      (node (ref "IC6") (pin "3") (pinfunction "+IN_3") (pintype "input"))
      (node (ref "R44") (pin "1-2") (pinfunction "S_1-2") (pintype "passive"))
      (node (ref "R45") (pin "1") (pinfunction "1_1") (pintype "passive"))
    )
    (net (code "38") (name "Net-(IC6A--IN)") (class "Default")
      (node (ref "IC6") (pin "2") (pinfunction "-IN_2") (pintype "input"))
      (node (ref "R53") (pin "2") (pinfunction "2_2") (pintype "passive"))
      (node (ref "R55") (pin "2") (pinfunction "2_2") (pintype "passive"))
      (node (ref "R59") (pin "1") (pinfunction "1_1") (pintype "passive"))
    )
    (net (code "39") (name "Net-(IC6A-OUT)") (class "Default")
      (node (ref "IC6") (pin "1") (pinfunction "OUT_1") (pintype "output"))
      (node (ref "IC7") (pin "2") (pinfunction "IN_2") (pintype "input"))
    )
    (net (code "40") (name "Net-(IC6B-+IN)") (class "Default")
      (node (ref "C51") (pin "1") (pinfunction "1_1") (pintype "passive"))
      (node (ref "IC6") (pin "5") (pinfunction "+IN_5") (pintype "input"))
      (node (ref "R56") (pin "2") (pinfunction "2_2") (pintype "passive"))
    )
    (net (code "41") (name "Net-(IC6B--IN)") (class "Default")
      (node (ref "C37") (pin "1") (pinfunction "1_1") (pintype "passive"))
      (node (ref "IC6") (pin "6") (pinfunction "-IN_6") (pintype "input"))
      (node (ref "R51") (pin "2") (pinfunction "2_2") (pintype "passive"))
    )
    (net (code "42") (name "Net-(IC6B-OUT)") (class "Default")
      (node (ref "C37") (pin "2") (pinfunction "2_2") (pintype "passive"))
      (node (ref "IC6") (pin "7") (pinfunction "OUT_7") (pintype "output"))
      (node (ref "R55") (pin "1") (pinfunction "1_1") (pintype "passive"))
    )
    (net (code "43") (name "Net-(IC6C-+IN)") (class "Default")
      (node (ref "IC6") (pin "10") (pinfunction "+IN_10") (pintype "input"))
      (node (ref "R44") (pin "2-2") (pinfunction "S_2-2") (pintype "passive"))
      (node (ref "R46") (pin "1") (pinfunction "1_1") (pintype "passive"))
    )
    (net (code "44") (name "Net-(IC6C--IN)") (class "Default")
      (node (ref "IC6") (pin "9") (pinfunction "-IN_9") (pintype "input"))
      (node (ref "R54") (pin "2") (pinfunction "2_2") (pintype "passive"))
      (node (ref "R57") (pin "2") (pinfunction "2_2") (pintype "passive"))
      (node (ref "R60") (pin "1") (pinfunction "1_1") (pintype "passive"))
    )
    (net (code "45") (name "Net-(IC6C-OUT)") (class "Default")
      (node (ref "IC6") (pin "8") (pinfunction "OUT_8") (pintype "output"))
      (node (ref "IC8") (pin "2") (pinfunction "IN_2") (pintype "input"))
    )
    (net (code "46") (name "Net-(IC6D-+IN)") (class "Default")
      (node (ref "C52") (pin "1") (pinfunction "1_1") (pintype "passive"))
      (node (ref "IC6") (pin "12") (pinfunction "+IN_12") (pintype "input"))
      (node (ref "R58") (pin "2") (pinfunction "2_2") (pintype "passive"))
    )
    (net (code "47") (name "Net-(IC6D--IN)") (class "Default")
      (node (ref "C38") (pin "1") (pinfunction "1_1") (pintype "passive"))
      (node (ref "IC6") (pin "13") (pinfunction "-IN_13") (pintype "input"))
      (node (ref "R52") (pin "2") (pinfunction "2_2") (pintype "passive"))
    )
    (net (code "48") (name "Net-(IC6D-OUT)") (class "Default")
      (node (ref "C38") (pin "2") (pinfunction "2_2") (pintype "passive"))
      (node (ref "IC6") (pin "14") (pinfunction "OUT_14") (pintype "output"))
      (node (ref "R57") (pin "1") (pinfunction "1_1") (pintype "passive"))
    )
    (net (code "49") (name "Net-(R9A-S)") (class "Default")
      (node (ref "R10") (pin "1") (pinfunction "1_1") (pintype "passive"))
      (node (ref "R13") (pin "2") (pinfunction "2_2") (pintype "passive"))
      (node (ref "R9") (pin "1-2") (pinfunction "S_1-2") (pintype "passive"))
    )
    (net (code "50") (name "Net-(R9B-S)") (class "Default")
      (node (ref "R11") (pin "1") (pinfunction "1_1") (pintype "passive"))
      (node (ref "R14") (pin "2") (pinfunction "2_2") (pintype "passive"))
      (node (ref "R9") (pin "2-2") (pinfunction "S_2-2") (pintype "passive"))
    )
    (net (code "51") (name "Net-(R22A-S)") (class "Default")
      (node (ref "R22") (pin "1-2") (pinfunction "S_1-2") (pintype "passive"))
      (node (ref "R27") (pin "1") (pinfunction "1_1") (pintype "passive"))
      (node (ref "R28") (pin "2") (pinfunction "2_2") (pintype "passive"))
    )
    (net (code "52") (name "Net-(R29-Pad1)") (class "Default")
      (node (ref "R29") (pin "1") (pinfunction "1_1") (pintype "passive"))
      (node (ref "U$17") (pin "P$1") (pinfunction "P$1_P$1") (pintype "bidirectional"))
    )
    (net (code "53") (name "Net-(R30-Pad1)") (class "Default")
      (node (ref "R30") (pin "1") (pinfunction "1_1") (pintype "passive"))
      (node (ref "U$19") (pin "P$1") (pinfunction "P$1_P$1") (pintype "bidirectional"))
    )
    (net (code "54") (name "Net-(R31-Pad1)") (class "Default")
      (node (ref "R31") (pin "1") (pinfunction "1_1") (pintype "passive"))
      (node (ref "U$14") (pin "P$1") (pinfunction "P$1_P$1") (pintype "bidirectional"))
    )
    (net (code "55") (name "Net-(R32-Pad1)") (class "Default")
      (node (ref "R32") (pin "1") (pinfunction "1_1") (pintype "passive"))
      (node (ref "U$16") (pin "P$1") (pinfunction "P$1_P$1") (pintype "bidirectional"))
    )
    (net (code "56") (name "Net-(U$1A-S)") (class "Default")
      (node (ref "C55") (pin "1") (pinfunction "1_1") (pintype "passive"))
      (node (ref "U$1") (pin "SB") (pinfunction "S_SB") (pintype "bidirectional"))
    )
    (net (code "57") (name "Net-(U$1A-T)") (class "Default")
      (node (ref "C9") (pin "1") (pinfunction "1_1") (pintype "passive"))
      (node (ref "S3") (pin "P$2") (pinfunction "P$2_P$2") (pintype "passive"))
      (node (ref "U$1") (pin "TB") (pinfunction "T_TB") (pintype "bidirectional"))
    )
    (net (code "58") (name "Net-(U$1B-S)") (class "Default")
      (node (ref "C53") (pin "1") (pinfunction "1_1") (pintype "passive"))
      (node (ref "U$1") (pin "ST") (pinfunction "S_ST") (pintype "bidirectional"))
    )
    (net (code "59") (name "Net-(U$1B-T)") (class "Default")
      (node (ref "C7") (pin "1") (pinfunction "1_1") (pintype "passive"))
      (node (ref "S1") (pin "P$2") (pinfunction "P$2_P$2") (pintype "passive"))
      (node (ref "U$1") (pin "TT") (pinfunction "T_TT") (pintype "bidirectional"))
    )
    (net (code "60") (name "Net-(U$2A-S)") (class "Default")
      (node (ref "C56") (pin "1") (pinfunction "1_1") (pintype "passive"))
      (node (ref "U$2") (pin "SB") (pinfunction "S_SB") (pintype "bidirectional"))
    )
    (net (code "61") (name "Net-(U$2A-T)") (class "Default")
      (node (ref "C10") (pin "1") (pinfunction "1_1") (pintype "passive"))
      (node (ref "S4") (pin "P$2") (pinfunction "P$2_P$2") (pintype "passive"))
      (node (ref "U$2") (pin "TB") (pinfunction "T_TB") (pintype "bidirectional"))
    )
    (net (code "62") (name "Net-(U$2B-S)") (class "Default")
      (node (ref "C54") (pin "1") (pinfunction "1_1") (pintype "passive"))
      (node (ref "U$2") (pin "ST") (pinfunction "S_ST") (pintype "bidirectional"))
    )
    (net (code "63") (name "Net-(U$2B-T)") (class "Default")
      (node (ref "C8") (pin "1") (pinfunction "1_1") (pintype "passive"))
      (node (ref "S2") (pin "P$2") (pinfunction "P$2_P$2") (pintype "passive"))
      (node (ref "U$2") (pin "TT") (pinfunction "T_TT") (pintype "bidirectional"))
    )
    (net (code "64") (name "Net-(U$3A-R)") (class "Default")
      (node (ref "R64") (pin "1") (pinfunction "1_1") (pintype "passive"))
      (node (ref "U$3") (pin "RB") (pinfunction "R_RB") (pintype "bidirectional"))
    )
    (net (code "65") (name "Net-(U$3A-T)") (class "Default")
      (node (ref "R63") (pin "1") (pinfunction "1_1") (pintype "passive"))
      (node (ref "U$3") (pin "TB") (pinfunction "T_TB") (pintype "bidirectional"))
    )
    (net (code "66") (name "Net-(U$3B-R)") (class "Default")
      (node (ref "R62") (pin "1") (pinfunction "1_1") (pintype "passive"))
      (node (ref "U$3") (pin "RT") (pinfunction "R_RT") (pintype "bidirectional"))
    )
    (net (code "67") (name "Net-(U$3B-T)") (class "Default")
      (node (ref "R61") (pin "1") (pinfunction "1_1") (pintype "passive"))
      (node (ref "U$3") (pin "TT") (pinfunction "T_TT") (pintype "bidirectional"))
    )
    (net (code "68") (name "Net-(U$4-FB)") (class "Default")
      (node (ref "C34") (pin "1") (pinfunction "1_1") (pintype "passive"))
      (node (ref "R49") (pin "1") (pinfunction "1_1") (pintype "passive"))
      (node (ref "R50") (pin "2") (pinfunction "2_2") (pintype "passive"))
      (node (ref "U$4") (pin "7") (pinfunction "FB_7") (pintype "bidirectional"))
    )
    (net (code "69") (name "Net-(U$4-NR{slash}SS)") (class "Default")
      (node (ref "C30") (pin "2") (pinfunction "2_2") (pintype "passive"))
      (node (ref "U$4") (pin "2") (pinfunction "NR/SS_2") (pintype "bidirectional"))
    )
    (net (code "70") (name "Net-(U$5-SENSE)") (class "Default")
      (node (ref "C33") (pin "1") (pinfunction "1_1") (pintype "passive"))
      (node (ref "R47") (pin "1") (pinfunction "1_1") (pintype "passive"))
      (node (ref "R48") (pin "2") (pinfunction "2_2") (pintype "passive"))
      (node (ref "U$5") (pin "5") (pinfunction "SENSE_5") (pintype "output"))
    )
    (net (code "71") (name "Net-(U$6B-S)") (class "Default")
      (node (ref "C57") (pin "1") (pinfunction "1_1") (pintype "passive"))
      (node (ref "U$6") (pin "ST") (pinfunction "S_ST") (pintype "bidirectional"))
    )
    (net (code "72") (name "Net-(U$6B-T)") (class "Default")
      (node (ref "C11") (pin "1") (pinfunction "1_1") (pintype "passive"))
      (node (ref "S5") (pin "P$2") (pinfunction "P$2_P$2") (pintype "passive"))
      (node (ref "U$6") (pin "TT") (pinfunction "T_TT") (pintype "bidirectional"))
    )
    (net (code "73") (name "Net-(U1-IN)") (class "Default")
      (node (ref "R20") (pin "1") (pinfunction "1_1") (pintype "passive"))
      (node (ref "U1") (pin "P4") (pinfunction "IN_P4") (pintype "input"))
    )
    (net (code "74") (name "Net-(U1-OUT+)") (class "Default")
      (node (ref "R29") (pin "2") (pinfunction "2_2") (pintype "passive"))
      (node (ref "U1") (pin "P7") (pinfunction "SENSE+_P7") (pintype "input"))
      (node (ref "U1") (pin "P8") (pinfunction "OUT+_P8") (pintype "output"))
    )
    (net (code "75") (name "Net-(U1-OUT-)") (class "Default")
      (node (ref "R30") (pin "2") (pinfunction "2_2") (pintype "passive"))
      (node (ref "U1") (pin "P1") (pinfunction "OUT-_P1") (pintype "output"))
      (node (ref "U1") (pin "P2") (pinfunction "SENSE-_P2") (pintype "input"))
    )
    (net (code "76") (name "Net-(U2-IN)") (class "Default")
      (node (ref "R21") (pin "1") (pinfunction "1_1") (pintype "passive"))
      (node (ref "U2") (pin "P4") (pinfunction "IN_P4") (pintype "input"))
    )
    (net (code "77") (name "Net-(U2-OUT+)") (class "Default")
      (node (ref "R31") (pin "2") (pinfunction "2_2") (pintype "passive"))
      (node (ref "U2") (pin "P7") (pinfunction "SENSE+_P7") (pintype "input"))
      (node (ref "U2") (pin "P8") (pinfunction "OUT+_P8") (pintype "output"))
    )
    (net (code "78") (name "Net-(U2-OUT-)") (class "Default")
      (node (ref "R32") (pin "2") (pinfunction "2_2") (pintype "passive"))
      (node (ref "U2") (pin "P1") (pinfunction "OUT-_P1") (pintype "output"))
      (node (ref "U2") (pin "P2") (pinfunction "SENSE-_P2") (pintype "input"))
    )
    (net (code "79") (name "Net-(U3-IN)") (class "Default")
      (node (ref "R36") (pin "1") (pinfunction "1_1") (pintype "passive"))
      (node (ref "U3") (pin "P4") (pinfunction "IN_P4") (pintype "input"))
    )
    (net (code "80") (name "Net-(U3-OUT+)") (class "Default")
      (node (ref "R61") (pin "2") (pinfunction "2_2") (pintype "passive"))
      (node (ref "U3") (pin "P7") (pinfunction "SENSE+_P7") (pintype "input"))
      (node (ref "U3") (pin "P8") (pinfunction "OUT+_P8") (pintype "output"))
    )
    (net (code "81") (name "Net-(U3-OUT-)") (class "Default")
      (node (ref "R62") (pin "2") (pinfunction "2_2") (pintype "passive"))
      (node (ref "U3") (pin "P1") (pinfunction "OUT-_P1") (pintype "output"))
      (node (ref "U3") (pin "P2") (pinfunction "SENSE-_P2") (pintype "input"))
    )
    (net (code "82") (name "Net-(U4-IN)") (class "Default")
      (node (ref "R37") (pin "1") (pinfunction "1_1") (pintype "passive"))
      (node (ref "U4") (pin "P4") (pinfunction "IN_P4") (pintype "input"))
    )
    (net (code "83") (name "Net-(U4-OUT+)") (class "Default")
      (node (ref "R63") (pin "2") (pinfunction "2_2") (pintype "passive"))
      (node (ref "U4") (pin "P7") (pinfunction "SENSE+_P7") (pintype "input"))
      (node (ref "U4") (pin "P8") (pinfunction "OUT+_P8") (pintype "output"))
    )
    (net (code "84") (name "Net-(U4-OUT-)") (class "Default")
      (node (ref "R64") (pin "2") (pinfunction "2_2") (pintype "passive"))
      (node (ref "U4") (pin "P1") (pinfunction "OUT-_P1") (pintype "output"))
      (node (ref "U4") (pin "P2") (pinfunction "SENSE-_P2") (pintype "input"))
    )
    (net (code "85") (name "V+") (class "Default")
      (node (ref "C2") (pin "1") (pinfunction "1_1") (pintype "passive"))
      (node (ref "C20") (pin "1") (pinfunction "1_1") (pintype "passive"))
      (node (ref "C22") (pin "1") (pinfunction "1_1") (pintype "passive"))
      (node (ref "C24") (pin "1") (pinfunction "1_1") (pintype "passive"))
      (node (ref "C33") (pin "2") (pinfunction "2_2") (pintype "passive"))
      (node (ref "C35") (pin "+") (pinfunction "+_+") (pintype "passive"))
      (node (ref "C39") (pin "1") (pinfunction "1_1") (pintype "passive"))
      (node (ref "C4") (pin "1") (pinfunction "1_1") (pintype "passive"))
      (node (ref "C40") (pin "1") (pinfunction "1_1") (pintype "passive"))
      (node (ref "C41") (pin "1") (pinfunction "1_1") (pintype "passive"))
      (node (ref "C42") (pin "1") (pinfunction "1_1") (pintype "passive"))
      (node (ref "C47") (pin "1") (pinfunction "1_1") (pintype "passive"))
      (node (ref "C49") (pin "1") (pinfunction "1_1") (pintype "passive"))
      (node (ref "C5") (pin "1") (pinfunction "1_1") (pintype "passive"))
      (node (ref "IC1") (pin "11") (pinfunction "V+_11") (pintype "power_in"))
      (node (ref "IC2") (pin "8") (pinfunction "V+_8") (pintype "power_in"))
      (node (ref "IC3") (pin "4") (pinfunction "V+_4") (pintype "power_in"))
      (node (ref "IC4") (pin "8") (pinfunction "V+_8") (pintype "power_in"))
      (node (ref "IC5") (pin "8") (pinfunction "V+_8") (pintype "power_in"))
      (node (ref "IC6") (pin "4") (pinfunction "V+_4") (pintype "power_in"))
      (node (ref "IC7") (pin "5") (pinfunction "VCC_5") (pintype "power_in"))
      (node (ref "IC8") (pin "5") (pinfunction "VCC_5") (pintype "power_in"))
      (node (ref "R47") (pin "2") (pinfunction "2_2") (pintype "passive"))
      (node (ref "U$5") (pin "4") (pinfunction "OUT_4") (pintype "power_in"))
      (node (ref "U1") (pin "P6") (pinfunction "V+_P6") (pintype "power_in"))
      (node (ref "U2") (pin "P6") (pinfunction "V+_P6") (pintype "power_in"))
      (node (ref "U3") (pin "P6") (pinfunction "V+_P6") (pintype "power_in"))
      (node (ref "U4") (pin "P6") (pinfunction "V+_P6") (pintype "power_in"))
    )
    (net (code "86") (name "V-") (class "Default")
      (node (ref "C1") (pin "2") (pinfunction "2_2") (pintype "passive"))
      (node (ref "C21") (pin "2") (pinfunction "2_2") (pintype "passive"))
      (node (ref "C23") (pin "2") (pinfunction "2_2") (pintype "passive"))
      (node (ref "C25") (pin "2") (pinfunction "2_2") (pintype "passive"))
      (node (ref "C3") (pin "2") (pinfunction "2_2") (pintype "passive"))
      (node (ref "C34") (pin "2") (pinfunction "2_2") (pintype "passive"))
      (node (ref "C36") (pin "-") (pinfunction "-_-") (pintype "passive"))
      (node (ref "C43") (pin "1") (pinfunction "1_1") (pintype "passive"))
      (node (ref "C44") (pin "1") (pinfunction "1_1") (pintype "passive"))
      (node (ref "C45") (pin "1") (pinfunction "1_1") (pintype "passive"))
      (node (ref "C46") (pin "1") (pinfunction "1_1") (pintype "passive"))
      (node (ref "C48") (pin "2") (pinfunction "2_2") (pintype "passive"))
      (node (ref "C50") (pin "2") (pinfunction "2_2") (pintype "passive"))
      (node (ref "C6") (pin "1") (pinfunction "1_1") (pintype "passive"))
      (node (ref "IC1") (pin "4") (pinfunction "V-_4") (pintype "power_in"))
      (node (ref "IC2") (pin "4") (pinfunction "V-_4") (pintype "power_in"))
      (node (ref "IC3") (pin "11") (pinfunction "V-_11") (pintype "power_in"))
      (node (ref "IC4") (pin "4") (pinfunction "V-_4") (pintype "power_in"))
      (node (ref "IC5") (pin "4") (pinfunction "V-_4") (pintype "power_in"))
      (node (ref "IC6") (pin "11") (pinfunction "V-_11") (pintype "power_in"))
      (node (ref "IC7") (pin "1") (pinfunction "BW_1") (pintype "input"))
      (node (ref "IC7") (pin "3") (pinfunction "VEE_3") (pintype "power_in"))
      (node (ref "IC7") (pin "TH@1") (pinfunction "VEE_TH@1") (pintype "power_in"))
      (node (ref "IC7") (pin "TH@2") (pinfunction "VEE_TH@2") (pintype "power_in"))
      (node (ref "IC8") (pin "1") (pinfunction "BW_1") (pintype "input"))
      (node (ref "IC8") (pin "3") (pinfunction "VEE_3") (pintype "power_in"))
      (node (ref "IC8") (pin "TH@1") (pinfunction "VEE_TH@1") (pintype "power_in"))
      (node (ref "IC8") (pin "TH@2") (pinfunction "VEE_TH@2") (pintype "power_in"))
      (node (ref "R49") (pin "2") (pinfunction "2_2") (pintype "passive"))
      (node (ref "U$4") (pin "6") (pinfunction "OUT_6") (pintype "bidirectional"))
      (node (ref "U1") (pin "P5") (pinfunction "V-_P5") (pintype "power_in"))
      (node (ref "U2") (pin "P5") (pinfunction "V-_P5") (pintype "power_in"))
      (node (ref "U3") (pin "P5") (pinfunction "V-_P5") (pintype "power_in"))
      (node (ref "U4") (pin "P5") (pinfunction "V-_P5") (pintype "power_in"))
    )
    (net (code "87") (name "unconnected-(IC1-NC-Pad1)") (class "Default")
      (node (ref "IC1") (pin "1") (pinfunction "NC_1") (pintype "no_connect"))
    )
    (net (code "88") (name "unconnected-(IC1-NC-Pad7)") (class "Default")
      (node (ref "IC1") (pin "7") (pinfunction "NC_7") (pintype "no_connect"))
    )
    (net (code "89") (name "unconnected-(U$1A-R-PadRB)") (class "Default")
      (node (ref "U$1") (pin "RB") (pinfunction "R_RB") (pintype "bidirectional"))
    )
    (net (code "90") (name "unconnected-(U$1A-RN-PadRNB)") (class "Default")
      (node (ref "U$1") (pin "RNB") (pinfunction "RN_RNB") (pintype "bidirectional"))
    )
    (net (code "91") (name "unconnected-(U$1A-SN-PadSNB)") (class "Default")
      (node (ref "U$1") (pin "SNB") (pinfunction "SN_SNB") (pintype "bidirectional"))
    )
    (net (code "92") (name "unconnected-(U$1A-TN-PadTNB)") (class "Default")
      (node (ref "U$1") (pin "TNB") (pinfunction "TN_TNB") (pintype "bidirectional"))
    )
    (net (code "93") (name "unconnected-(U$1B-R-PadRT)") (class "Default")
      (node (ref "U$1") (pin "RT") (pinfunction "R_RT") (pintype "bidirectional"))
    )
    (net (code "94") (name "unconnected-(U$1B-RN-PadRNT)") (class "Default")
      (node (ref "U$1") (pin "RNT") (pinfunction "RN_RNT") (pintype "bidirectional"))
    )
    (net (code "95") (name "unconnected-(U$1B-SN-PadSNT)") (class "Default")
      (node (ref "U$1") (pin "SNT") (pinfunction "SN_SNT") (pintype "bidirectional"))
    )
    (net (code "96") (name "unconnected-(U$1B-TN-PadTNT)") (class "Default")
      (node (ref "U$1") (pin "TNT") (pinfunction "TN_TNT") (pintype "bidirectional"))
    )
    (net (code "97") (name "unconnected-(U$2A-R-PadRB)") (class "Default")
      (node (ref "U$2") (pin "RB") (pinfunction "R_RB") (pintype "bidirectional"))
    )
    (net (code "98") (name "unconnected-(U$2A-RN-PadRNB)") (class "Default")
      (node (ref "U$2") (pin "RNB") (pinfunction "RN_RNB") (pintype "bidirectional"))
    )
    (net (code "99") (name "unconnected-(U$2A-SN-PadSNB)") (class "Default")
      (node (ref "U$2") (pin "SNB") (pinfunction "SN_SNB") (pintype "bidirectional"))
    )
    (net (code "100") (name "unconnected-(U$2A-TN-PadTNB)") (class "Default")
      (node (ref "U$2") (pin "TNB") (pinfunction "TN_TNB") (pintype "bidirectional"))
    )
    (net (code "101") (name "unconnected-(U$2B-R-PadRT)") (class "Default")
      (node (ref "U$2") (pin "RT") (pinfunction "R_RT") (pintype "bidirectional"))
    )
    (net (code "102") (name "unconnected-(U$2B-RN-PadRNT)") (class "Default")
      (node (ref "U$2") (pin "RNT") (pinfunction "RN_RNT") (pintype "bidirectional"))
    )
    (net (code "103") (name "unconnected-(U$2B-SN-PadSNT)") (class "Default")
      (node (ref "U$2") (pin "SNT") (pinfunction "SN_SNT") (pintype "bidirectional"))
    )
    (net (code "104") (name "unconnected-(U$2B-TN-PadTNT)") (class "Default")
      (node (ref "U$2") (pin "TNT") (pinfunction "TN_TNT") (pintype "bidirectional"))
    )
    (net (code "105") (name "unconnected-(U$3A-RN-PadRNB)") (class "Default")
      (node (ref "U$3") (pin "RNB") (pinfunction "RN_RNB") (pintype "bidirectional"))
    )
    (net (code "106") (name "unconnected-(U$3A-SN-PadSNB)") (class "Default")
      (node (ref "U$3") (pin "SNB") (pinfunction "SN_SNB") (pintype "bidirectional"))
    )
    (net (code "107") (name "unconnected-(U$3A-TN-PadTNB)") (class "Default")
      (node (ref "U$3") (pin "TNB") (pinfunction "TN_TNB") (pintype "bidirectional"))
    )
    (net (code "108") (name "unconnected-(U$3B-RN-PadRNT)") (class "Default")
      (node (ref "U$3") (pin "RNT") (pinfunction "RN_RNT") (pintype "bidirectional"))
    )
    (net (code "109") (name "unconnected-(U$3B-SN-PadSNT)") (class "Default")
      (node (ref "U$3") (pin "SNT") (pinfunction "SN_SNT") (pintype "bidirectional"))
    )
    (net (code "110") (name "unconnected-(U$3B-TN-PadTNT)") (class "Default")
      (node (ref "U$3") (pin "TNT") (pinfunction "TN_TNT") (pintype "bidirectional"))
    )
    (net (code "111") (name "unconnected-(U$6A-RN-PadRNB)") (class "Default")
      (node (ref "U$6") (pin "RNB") (pinfunction "RN_RNB") (pintype "bidirectional"))
    )
    (net (code "112") (name "unconnected-(U$6A-SN-PadSNB)") (class "Default")
      (node (ref "U$6") (pin "SNB") (pinfunction "SN_SNB") (pintype "bidirectional"))
    )
    (net (code "113") (name "unconnected-(U$6A-TN-PadTNB)") (class "Default")
      (node (ref "U$6") (pin "TNB") (pinfunction "TN_TNB") (pintype "bidirectional"))
    )
    (net (code "114") (name "unconnected-(U$6B-R-PadRT)") (class "Default")
      (node (ref "U$6") (pin "RT") (pinfunction "R_RT") (pintype "bidirectional"))
    )
    (net (code "115") (name "unconnected-(U$6B-RN-PadRNT)") (class "Default")
      (node (ref "U$6") (pin "RNT") (pinfunction "RN_RNT") (pintype "bidirectional"))
    )
    (net (code "116") (name "unconnected-(U$6B-SN-PadSNT)") (class "Default")
      (node (ref "U$6") (pin "SNT") (pinfunction "SN_SNT") (pintype "bidirectional"))
    )
    (net (code "117") (name "unconnected-(U$6B-TN-PadTNT)") (class "Default")
      (node (ref "U$6") (pin "TNT") (pinfunction "TN_TNT") (pintype "bidirectional"))
    )
  )
)
